# Microcontroller_and_Power_Management.net
KiCad netlist of a schematic drawn in Altium Designer
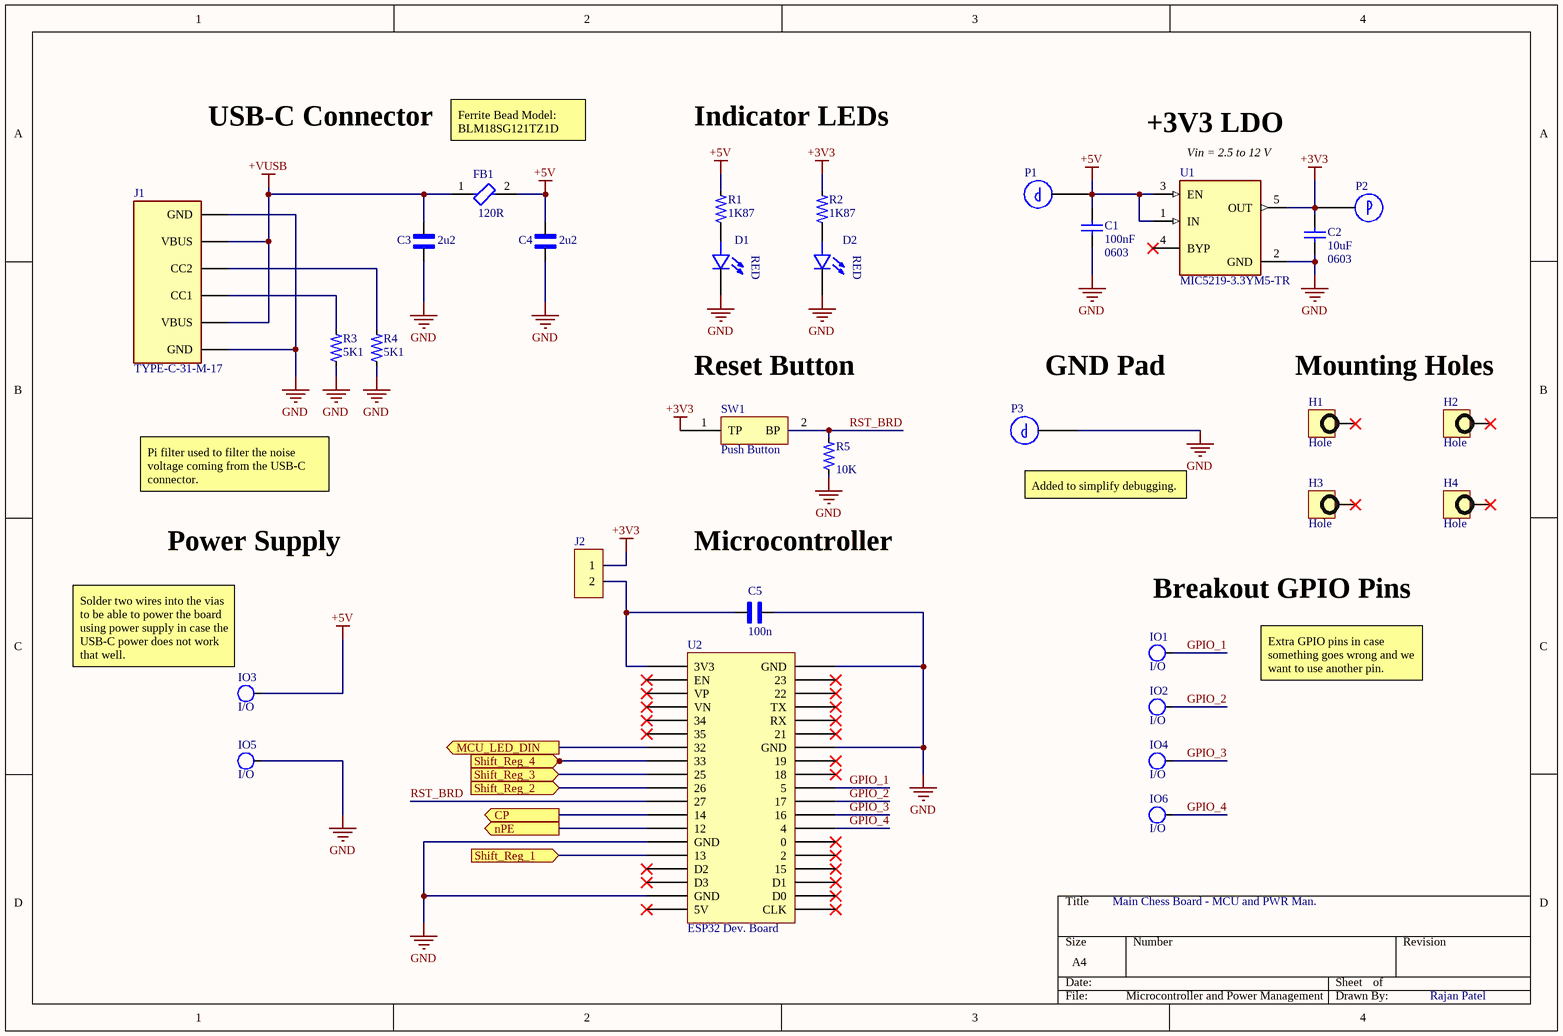
[diagram p0: Microcontroller and Power Management.SchDoc]

(export (version "E")
  (design (tool "Eeschema 10.0.6"))
  (components
    (comp (ref "C1")
      (value "100nF")
      (footprint "CAP 0805")
      (description "Capacitor")
      (fields (field (name "ALTIUM_VALUE") "0603") (field (name "PUBLISHER") "Altium Limited"))
      (libsource (lib "Miscellaneous Devices") (part "Cap"))
    )
    (comp (ref "C2")
      (value "10uF")
      (footprint "CAP 0805")
      (description "Capacitor")
      (fields (field (name "ALTIUM_VALUE") "0603") (field (name "PUBLISHER") "Altium Limited"))
      (libsource (lib "Miscellaneous Devices") (part "Cap"))
    )
    (comp (ref "C3")
      (value "2u2")
      (footprint "CAP 0805")
      (libsource (lib "ChessBoardSchLib") (part "CAP 0805"))
    )
    (comp (ref "C4")
      (value "2u2")
      (footprint "CAP 0805")
      (libsource (lib "ChessBoardSchLib") (part "CAP 0805"))
    )
    (comp (ref "C5")
      (value "100n")
      (footprint "CAP 0805")
      (libsource (lib "ChessBoardSchLib") (part "CAP 0805"))
    )
    (comp (ref "D1")
      (value "LED 0805")
      (footprint "LED_0805")
      (description "Red LED Indication - Discrete 1.7V 0805 (2012 Metric)")
      (fields (field (name "MP") "7012X1"))
      (libsource (lib "ChessBoardSchLib") (part "LED 0805"))
    )
    (comp (ref "D2")
      (value "LED 0805")
      (footprint "LED_0805")
      (description "Red LED Indication - Discrete 1.7V 0805 (2012 Metric)")
      (fields (field (name "MP") "7012X1"))
      (libsource (lib "ChessBoardSchLib") (part "LED 0805"))
    )
    (comp (ref "FB1")
      (value "120R")
      (footprint "FP-BLM21-0_2-t0_85-e0_5-IPC_A")
      (description "FERRITE BEAD 120 OHM 0603 1LN")
      (fields (field (name "TOLERANCE") "25%"))
      (libsource (lib "Altium Content Vault") (part "5f30dd21d616792df468990f7003faa"))
    )
    (comp (ref "H1") (value "Hole") (footprint "M3 Holes") (libsource (lib "MRT SCH Library") (part "Hole")))
    (comp (ref "H2") (value "Hole") (footprint "M3 Holes") (libsource (lib "MRT SCH Library") (part "Hole")))
    (comp (ref "H3") (value "Hole") (footprint "M3 Holes") (libsource (lib "MRT SCH Library") (part "Hole")))
    (comp (ref "H4") (value "Hole") (footprint "M3 Holes") (libsource (lib "MRT SCH Library") (part "Hole")))
    (comp (ref "IO1") (value "I/O") (footprint "I/O") (libsource (lib "MiniChessBoardSchLib") (part "I/O")))
    (comp (ref "IO2") (value "I/O") (footprint "I/O") (libsource (lib "MiniChessBoardSchLib") (part "I/O")))
    (comp (ref "IO3") (value "I/O") (footprint "I/O") (libsource (lib "MiniChessBoardSchLib") (part "I/O")))
    (comp (ref "IO4") (value "I/O") (footprint "I/O") (libsource (lib "MiniChessBoardSchLib") (part "I/O")))
    (comp (ref "IO5") (value "I/O") (footprint "I/O") (libsource (lib "MiniChessBoardSchLib") (part "I/O")))
    (comp (ref "IO6") (value "I/O") (footprint "I/O") (libsource (lib "MiniChessBoardSchLib") (part "I/O")))
    (comp (ref "J1")
      (value "TYPE-C-31-M-17")
      (footprint "TYPEC31M17")
      (description "TYPE-C-31-M-17 HROPARTS")
      (fields (field (name "MF") "HRO Electronics Co., Ltd."))
      (libsource (lib "ChessBoardSchLib") (part "TYPE-C-31-M-17"))
    )
    (comp (ref "J2")
      (value "2 Pin Male Header")
      (footprint "2 Pin Male Header")
      (fields
        (field (name "MANUFACTURER") "TE Connectivity")
        (field (name "MANUFACTURER PART NUMBER") "5-146277-2")
      )
      (libsource (lib "ChessBoardSchLib") (part "2 Pin Male Header"))
    )
    (comp (ref "P1")
      (value "Probe_5019")
      (footprint "Testpoint")
      (description "Phosphor Bronze Contact Miniature Silver Plated Surface Mount Test Points")
      (fields
        (field (name "MANUFACTURER") "Keystone Electronics")
        (field (name "MANUFACTURER PART NUMBER") "5019")
      )
      (libsource (lib "MiniChessBoardSchLib") (part "Probe_5019"))
    )
    (comp (ref "P2")
      (value "Probe_5019")
      (footprint "Testpoint")
      (description "Phosphor Bronze Contact Miniature Silver Plated Surface Mount Test Points")
      (fields
        (field (name "MANUFACTURER") "Keystone Electronics")
        (field (name "MANUFACTURER PART NUMBER") "5019")
      )
      (libsource (lib "MiniChessBoardSchLib") (part "Probe_5019"))
    )
    (comp (ref "P3")
      (value "Probe_5019")
      (footprint "Testpoint")
      (description "Phosphor Bronze Contact Miniature Silver Plated Surface Mount Test Points")
      (fields
        (field (name "MANUFACTURER") "Keystone Electronics")
        (field (name "MANUFACTURER PART NUMBER") "5019")
      )
      (libsource (lib "MiniChessBoardSchLib") (part "Probe_5019"))
    )
    (comp (ref "R1")
      (value "1K87")
      (footprint "res 0805")
      (fields
        (field (name "MP") "2-2176053-2")
        (field (name "MF") "TE Connectivity")
        (field (name "TOLERANCE") "1%")
      )
      (libsource (lib "ChessBoardSchLib") (part "Resistor 0805"))
    )
    (comp (ref "R2")
      (value "1K87")
      (footprint "res 0805")
      (fields
        (field (name "MP") "2-2176053-2")
        (field (name "MF") "TE Connectivity")
        (field (name "TOLERANCE") "1%")
      )
      (libsource (lib "ChessBoardSchLib") (part "Resistor 0805"))
    )
    (comp (ref "R3")
      (value "5K1")
      (footprint "res 0805")
      (fields
        (field (name "MP") "2-2176053-2")
        (field (name "MF") "TE Connectivity")
        (field (name "TOLERANCE") "1%")
      )
      (libsource (lib "ChessBoardSchLib") (part "Resistor 0805"))
    )
    (comp (ref "R4")
      (value "5K1")
      (footprint "res 0805")
      (fields
        (field (name "MP") "2-2176053-2")
        (field (name "MF") "TE Connectivity")
        (field (name "TOLERANCE") "1%")
      )
      (libsource (lib "ChessBoardSchLib") (part "Resistor 0805"))
    )
    (comp (ref "R5")
      (value "10K")
      (footprint "res 0805")
      (fields
        (field (name "MP") "2-2176053-2")
        (field (name "MF") "TE Connectivity")
        (field (name "TOLERANCE") "1%")
      )
      (libsource (lib "ChessBoardSchLib") (part "Resistor 0805"))
    )
    (comp (ref "SW1")
      (value "Push Button")
      (footprint "Push Button")
      (libsource (lib "ChessBoardSchLib") (part "Push Button"))
    )
    (comp (ref "U1")
      (value "MIC5219-3.3YM5-TR")
      (footprint "FP-SOT23-5LD-PL-1-IPC_C")
      (description "IC REG LINEAR 3.3V 500MA SOT23-5")
      (libsource (lib "Altium Content Vault") (part "16b36b16d6b7b40c29ab14718bc3058"))
    )
    (comp (ref "U2")
      (value "ESP32 Dev. Board")
      (footprint "ESPRESSIF_ESP32-DEVKITC-32UE")
      (fields
        (field (name "MANUFACTURER") "Espressif Systems")
        (field (name "MANUFACTURER PART NUMBER") "ESP32-DEVKITC-32UE")
      )
      (libsource (lib "ChessBoardSchLib") (part "ESP32 Dev. Board"))
    )
  )
  (nets
    (net (code "1") (name "+3V3") (class "Default")
      (node (ref "C2") (pin "2") (pinfunction "2_2") (pintype "passive"))
      (node (ref "J2") (pin "1") (pinfunction "1_1") (pintype "passive"))
      (node (ref "P2") (pin "1") (pinfunction "1_1") (pintype "passive"))
      (node (ref "R2") (pin "2") (pinfunction "2_2") (pintype "passive"))
      (node (ref "SW1") (pin "1") (pinfunction "TP_1") (pintype "passive"))
      (node (ref "U1") (pin "5") (pinfunction "OUT_5") (pintype "output"))
    )
    (net (code "2") (name "+5V") (class "Default")
      (node (ref "C1") (pin "2") (pinfunction "2_2") (pintype "passive"))
      (node (ref "C4") (pin "2") (pinfunction "2_2") (pintype "passive"))
      (node (ref "FB1") (pin "2") (pinfunction "2_2") (pintype "passive"))
      (node (ref "IO3") (pin "1") (pinfunction "1_1") (pintype "passive"))
      (node (ref "P1") (pin "1") (pinfunction "1_1") (pintype "passive"))
      (node (ref "R1") (pin "2") (pinfunction "2_2") (pintype "passive"))
      (node (ref "U1") (pin "1") (pinfunction "IN_1") (pintype "input"))
      (node (ref "U1") (pin "3") (pinfunction "EN_3") (pintype "input"))
    )
    (net (code "3") (name "+VUSB") (class "Default")
      (node (ref "C3") (pin "2") (pinfunction "2_2") (pintype "passive"))
      (node (ref "FB1") (pin "1") (pinfunction "1_1") (pintype "passive"))
      (node (ref "J1") (pin "2") (pinfunction "VBUS_2") (pintype "passive"))
      (node (ref "J1") (pin "5") (pinfunction "VBUS_5") (pintype "passive"))
    )
    (net (code "4") (name "/CP") (class "Default")
      (node (ref "U2") (pin "12") (pinfunction "14_12") (pintype "passive"))
    )
    (net (code "5") (name "/GPIO_1") (class "Default")
      (node (ref "IO1") (pin "1") (pinfunction "1_1") (pintype "passive"))
      (node (ref "U2") (pin "29") (pinfunction "5_29") (pintype "passive"))
    )
    (net (code "6") (name "/GPIO_2") (class "Default")
      (node (ref "IO2") (pin "1") (pinfunction "1_1") (pintype "passive"))
      (node (ref "U2") (pin "28") (pinfunction "17_28") (pintype "passive"))
    )
    (net (code "7") (name "/GPIO_3") (class "Default")
      (node (ref "IO4") (pin "1") (pinfunction "1_1") (pintype "passive"))
      (node (ref "U2") (pin "27") (pinfunction "16_27") (pintype "passive"))
    )
    (net (code "8") (name "/GPIO_4") (class "Default")
      (node (ref "IO6") (pin "1") (pinfunction "1_1") (pintype "passive"))
      (node (ref "U2") (pin "26") (pinfunction "4_26") (pintype "passive"))
    )
    (net (code "9") (name "/MCU_LED_DIN") (class "Default")
      (node (ref "U2") (pin "7") (pinfunction "32_7") (pintype "passive"))
    )
    (net (code "10") (name "/RST_BRD") (class "Default")
      (node (ref "R5") (pin "2") (pinfunction "2_2") (pintype "passive"))
      (node (ref "SW1") (pin "2") (pinfunction "BP_2") (pintype "passive"))
      (node (ref "U2") (pin "11") (pinfunction "27_11") (pintype "passive"))
    )
    (net (code "11") (name "/Shift_Reg_1") (class "Default")
      (node (ref "U2") (pin "15") (pinfunction "13_15") (pintype "passive"))
    )
    (net (code "12") (name "/Shift_Reg_2") (class "Default")
      (node (ref "U2") (pin "10") (pinfunction "26_10") (pintype "passive"))
    )
    (net (code "13") (name "/Shift_Reg_3") (class "Default")
      (node (ref "U2") (pin "9") (pinfunction "25_9") (pintype "passive"))
    )
    (net (code "14") (name "/Shift_Reg_4") (class "Default")
      (node (ref "U2") (pin "8") (pinfunction "33_8") (pintype "passive"))
    )
    (net (code "15") (name "/nPE") (class "Default")
      (node (ref "U2") (pin "13") (pinfunction "12_13") (pintype "passive"))
    )
    (net (code "16") (name "GND") (class "Default")
      (node (ref "C1") (pin "1") (pinfunction "1_1") (pintype "passive"))
      (node (ref "C2") (pin "1") (pinfunction "1_1") (pintype "passive"))
      (node (ref "C3") (pin "1") (pinfunction "1_1") (pintype "passive"))
      (node (ref "C4") (pin "1") (pinfunction "1_1") (pintype "passive"))
      (node (ref "C5") (pin "1") (pinfunction "1_1") (pintype "passive"))
      (node (ref "D1") (pin "1") (pinfunction "C_1") (pintype "passive"))
      (node (ref "D2") (pin "1") (pinfunction "C_1") (pintype "passive"))
      (node (ref "IO5") (pin "1") (pinfunction "1_1") (pintype "passive"))
      (node (ref "J1") (pin "1") (pinfunction "GND_1") (pintype "passive"))
      (node (ref "J1") (pin "6") (pinfunction "GND_6") (pintype "passive"))
      (node (ref "P3") (pin "1") (pinfunction "1_1") (pintype "passive"))
      (node (ref "R3") (pin "1") (pinfunction "1_1") (pintype "passive"))
      (node (ref "R4") (pin "1") (pinfunction "1_1") (pintype "passive"))
      (node (ref "R5") (pin "1") (pinfunction "1_1") (pintype "passive"))
      (node (ref "U1") (pin "2") (pinfunction "GND_2") (pintype "power_in"))
      (node (ref "U2") (pin "14") (pinfunction "GND_14") (pintype "passive"))
      (node (ref "U2") (pin "18") (pinfunction "GND_18") (pintype "passive"))
      (node (ref "U2") (pin "32") (pinfunction "GND_32") (pintype "passive"))
      (node (ref "U2") (pin "38") (pinfunction "GND_38") (pintype "passive"))
    )
    (net (code "17") (name "Net-(D1-A)") (class "Default")
      (node (ref "D1") (pin "2") (pinfunction "A_2") (pintype "passive"))
      (node (ref "R1") (pin "1") (pinfunction "1_1") (pintype "passive"))
    )
    (net (code "18") (name "Net-(D2-A)") (class "Default")
      (node (ref "D2") (pin "2") (pinfunction "A_2") (pintype "passive"))
      (node (ref "R2") (pin "1") (pinfunction "1_1") (pintype "passive"))
    )
    (net (code "19") (name "Net-(J1-CC1)") (class "Default")
      (node (ref "J1") (pin "3") (pinfunction "CC1_3") (pintype "passive"))
      (node (ref "R3") (pin "2") (pinfunction "2_2") (pintype "passive"))
    )
    (net (code "20") (name "Net-(J1-CC2)") (class "Default")
      (node (ref "J1") (pin "4") (pinfunction "CC2_4") (pintype "passive"))
      (node (ref "R4") (pin "2") (pinfunction "2_2") (pintype "passive"))
    )
    (net (code "21") (name "Net-(U2-3V3)") (class "Default")
      (node (ref "C5") (pin "2") (pinfunction "2_2") (pintype "passive"))
      (node (ref "J2") (pin "2") (pinfunction "2_2") (pintype "passive"))
      (node (ref "U2") (pin "1") (pinfunction "3V3_1") (pintype "passive"))
    )
    (net (code "22") (name "unconnected-(H1-TERMINAL-Pad1)") (class "Default")
      (node (ref "H1") (pin "1") (pinfunction "TERMINAL_1") (pintype "passive+no_connect"))
    )
    (net (code "23") (name "unconnected-(H2-TERMINAL-Pad1)") (class "Default")
      (node (ref "H2") (pin "1") (pinfunction "TERMINAL_1") (pintype "passive+no_connect"))
    )
    (net (code "24") (name "unconnected-(H3-TERMINAL-Pad1)") (class "Default")
      (node (ref "H3") (pin "1") (pinfunction "TERMINAL_1") (pintype "passive+no_connect"))
    )
    (net (code "25") (name "unconnected-(H4-TERMINAL-Pad1)") (class "Default")
      (node (ref "H4") (pin "1") (pinfunction "TERMINAL_1") (pintype "passive+no_connect"))
    )
    (net (code "26") (name "unconnected-(U1-BYP-Pad4)") (class "Default")
      (node (ref "U1") (pin "4") (pinfunction "BYP_4") (pintype "passive+no_connect"))
    )
    (net (code "27") (name "unconnected-(U2-0-Pad25)") (class "Default")
      (node (ref "U2") (pin "25") (pinfunction "0_25") (pintype "passive+no_connect"))
    )
    (net (code "28") (name "unconnected-(U2-2-Pad24)") (class "Default")
      (node (ref "U2") (pin "24") (pinfunction "2_24") (pintype "passive+no_connect"))
    )
    (net (code "29") (name "unconnected-(U2-5V-Pad19)") (class "Default")
      (node (ref "U2") (pin "19") (pinfunction "5V_19") (pintype "passive+no_connect"))
    )
    (net (code "30") (name "unconnected-(U2-15-Pad23)") (class "Default")
      (node (ref "U2") (pin "23") (pinfunction "15_23") (pintype "passive+no_connect"))
    )
    (net (code "31") (name "unconnected-(U2-18-Pad30)") (class "Default")
      (node (ref "U2") (pin "30") (pinfunction "18_30") (pintype "passive+no_connect"))
    )
    (net (code "32") (name "unconnected-(U2-19-Pad31)") (class "Default")
      (node (ref "U2") (pin "31") (pinfunction "19_31") (pintype "passive+no_connect"))
    )
    (net (code "33") (name "unconnected-(U2-21-Pad33)") (class "Default")
      (node (ref "U2") (pin "33") (pinfunction "21_33") (pintype "passive+no_connect"))
    )
    (net (code "34") (name "unconnected-(U2-22-Pad36)") (class "Default")
      (node (ref "U2") (pin "36") (pinfunction "22_36") (pintype "passive+no_connect"))
    )
    (net (code "35") (name "unconnected-(U2-23-Pad37)") (class "Default")
      (node (ref "U2") (pin "37") (pinfunction "23_37") (pintype "passive+no_connect"))
    )
    (net (code "36") (name "unconnected-(U2-34-Pad5)") (class "Default")
      (node (ref "U2") (pin "5") (pinfunction "34_5") (pintype "passive+no_connect"))
    )
    (net (code "37") (name "unconnected-(U2-35-Pad6)") (class "Default")
      (node (ref "U2") (pin "6") (pinfunction "35_6") (pintype "passive+no_connect"))
    )
    (net (code "38") (name "unconnected-(U2-CLK-Pad20)") (class "Default")
      (node (ref "U2") (pin "20") (pinfunction "CLK_20") (pintype "passive+no_connect"))
    )
    (net (code "39") (name "unconnected-(U2-D0-Pad21)") (class "Default")
      (node (ref "U2") (pin "21") (pinfunction "D0_21") (pintype "passive+no_connect"))
    )
    (net (code "40") (name "unconnected-(U2-D1-Pad22)") (class "Default")
      (node (ref "U2") (pin "22") (pinfunction "D1_22") (pintype "passive+no_connect"))
    )
    (net (code "41") (name "unconnected-(U2-D2-Pad16)") (class "Default")
      (node (ref "U2") (pin "16") (pinfunction "D2_16") (pintype "passive+no_connect"))
    )
    (net (code "42") (name "unconnected-(U2-D3-Pad17)") (class "Default")
      (node (ref "U2") (pin "17") (pinfunction "D3_17") (pintype "passive+no_connect"))
    )
    (net (code "43") (name "unconnected-(U2-EN-Pad2)") (class "Default")
      (node (ref "U2") (pin "2") (pinfunction "EN_2") (pintype "passive+no_connect"))
    )
    (net (code "44") (name "unconnected-(U2-RX-Pad34)") (class "Default")
      (node (ref "U2") (pin "34") (pinfunction "RX_34") (pintype "passive+no_connect"))
    )
    (net (code "45") (name "unconnected-(U2-TX-Pad35)") (class "Default")
      (node (ref "U2") (pin "35") (pinfunction "TX_35") (pintype "passive+no_connect"))
    )
    (net (code "46") (name "unconnected-(U2-VN-Pad4)") (class "Default")
      (node (ref "U2") (pin "4") (pinfunction "VN_4") (pintype "passive+no_connect"))
    )
    (net (code "47") (name "unconnected-(U2-VP-Pad3)") (class "Default")
      (node (ref "U2") (pin "3") (pinfunction "VP_3") (pintype "passive+no_connect"))
    )
  )
)
